# Pico_T61_Keyboard_R1.net
KiCad netlist of a schematic drawn in EAGLE
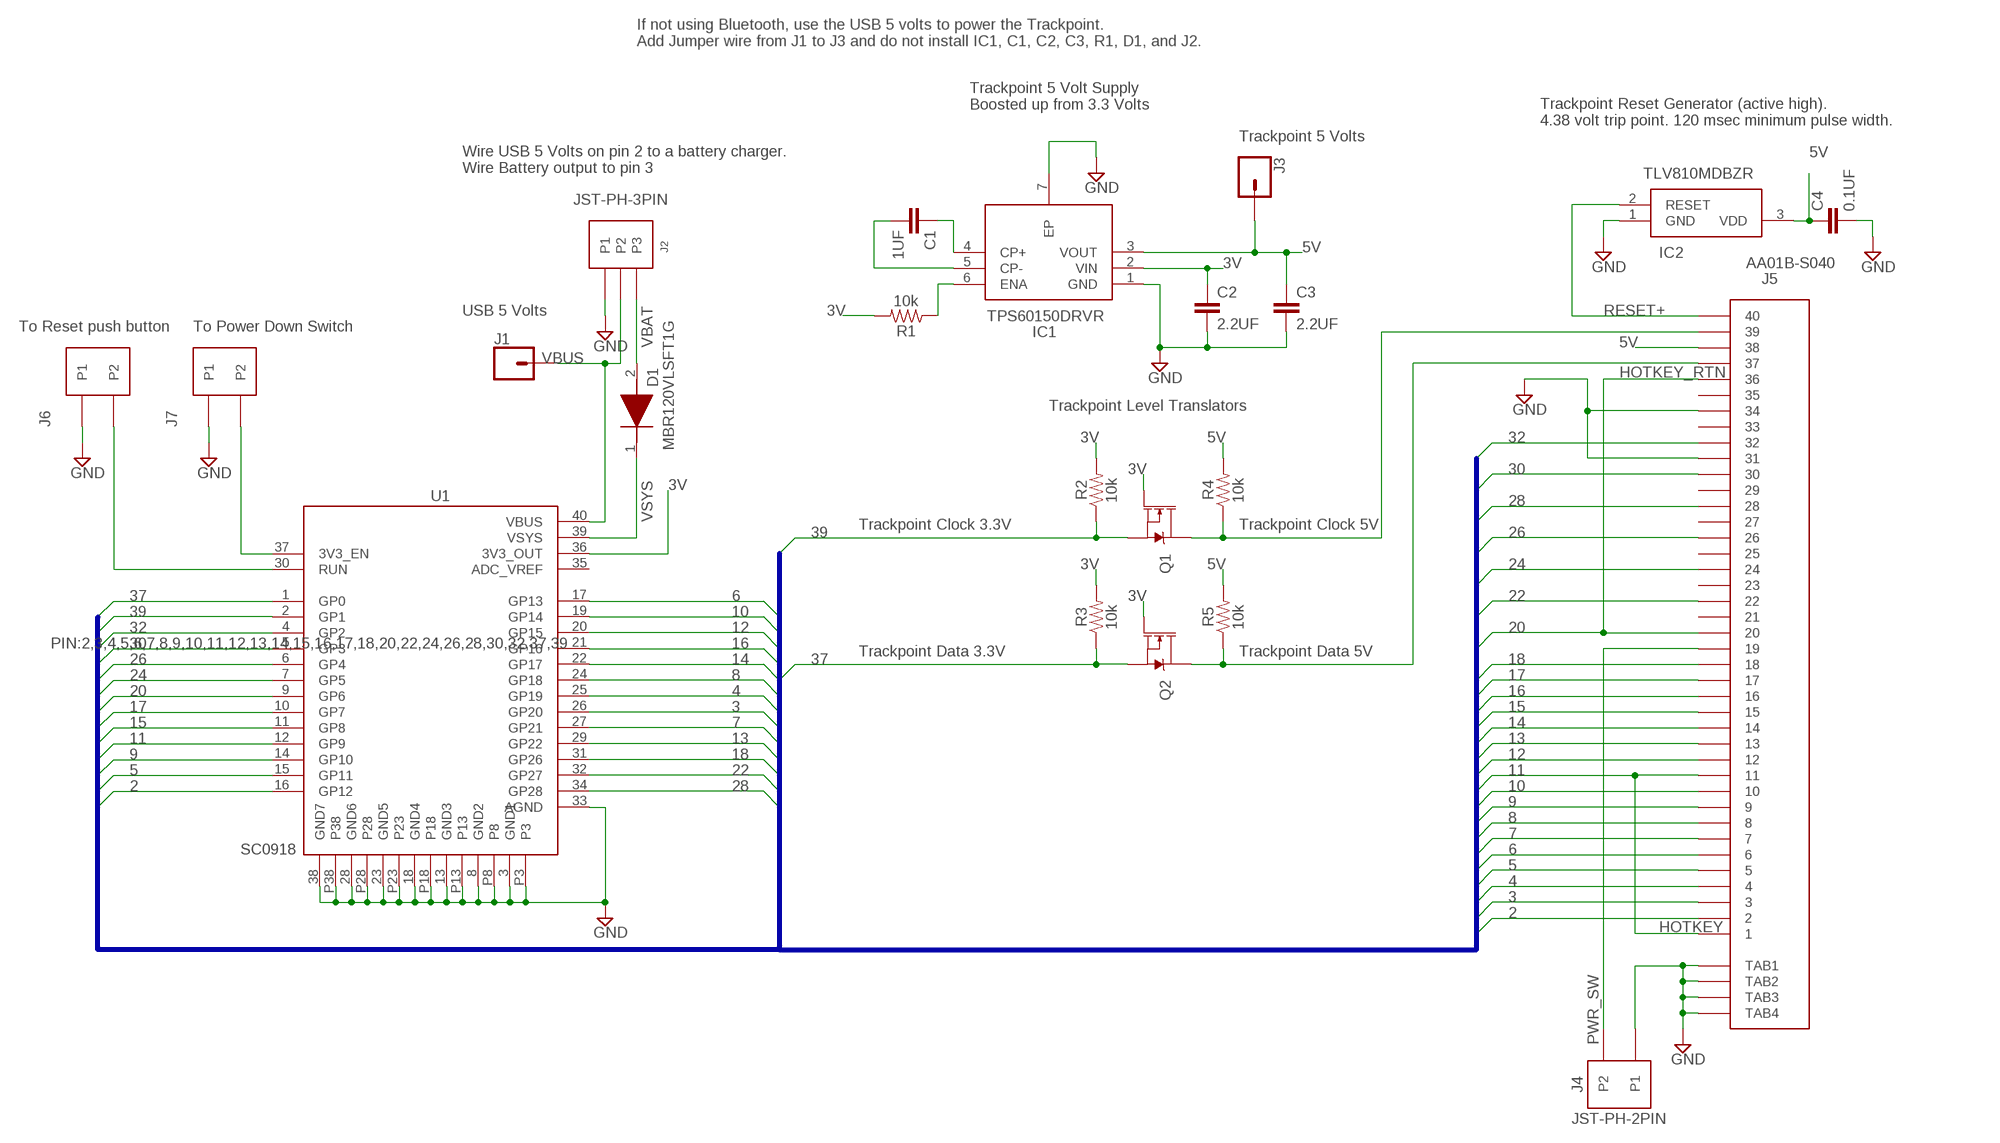
[diagram p0: schematic, sheet 1]

(export (version "E")
  (design (tool "Eeschema 10.0.6"))
  (components
    (comp (ref "C1")
      (value "1UF")
      (footprint "eagle-import:0603_CAP")
      (libsource (lib "eagle-import") (part "0603_CAP"))
    )
    (comp (ref "C2")
      (value "2.2UF")
      (footprint "eagle-import:0603_CAP")
      (libsource (lib "eagle-import") (part "0603_CAP"))
    )
    (comp (ref "C3")
      (value "2.2UF")
      (footprint "eagle-import:0603_CAP")
      (libsource (lib "eagle-import") (part "0603_CAP"))
    )
    (comp (ref "C4")
      (value "0.1UF")
      (footprint "eagle-import:0603_CAP")
      (libsource (lib "eagle-import") (part "0603_CAP"))
    )
    (comp (ref "D1")
      (value "MBR120VLSFT1G")
      (footprint "eagle-import:SODFL3616X98N")
      (fields (field (name "MOUSER_PART_NUMBER") "863-MBR120VLSFT1G"))
      (libsource (lib "eagle-import") (part "MBR120VLSFT1G"))
    )
    (comp (ref "IC1")
      (value "TPS60150DRVR")
      (footprint "eagle-import:SON65P200X200X80-7N")
      (fields (field (name "MOUSER_PART_NUMBER") "595-TPS60150DRVR"))
      (libsource (lib "eagle-import") (part "TPS60150DRVR"))
    )
    (comp (ref "IC2")
      (value "TLV810MDBZR")
      (footprint "eagle-import:SOT95P237X112-3N")
      (fields (field (name "MOUSER_PART_NUMBER") "595-TLV810MDBZR"))
      (libsource (lib "eagle-import") (part "TLV810MDBZR"))
    )
    (comp (ref "J1")
      (value "CONN_01")
      (footprint "eagle-import:1X01")
      (libsource (lib "eagle-import") (part "CONN_01"))
    )
    (comp (ref "J2")
      (value "JST-PH-3PIN")
      (footprint "eagle-import:JST-PH-3PIN")
      (libsource (lib "eagle-import") (part "JST-PH-3PIN"))
    )
    (comp (ref "J3")
      (value "CONN_01")
      (footprint "eagle-import:1X01")
      (libsource (lib "eagle-import") (part "CONN_01"))
    )
    (comp (ref "J4")
      (value "JST-PH-2PIN")
      (footprint "eagle-import:JST-PH-2PIN")
      (libsource (lib "eagle-import") (part "JST-PH-2PIN"))
    )
    (comp (ref "J5")
      (value "AA01B-S040")
      (footprint "eagle-import:WM6787_AA01B")
      (libsource (lib "eagle-import") (part "WM6787_A01B"))
    )
    (comp (ref "J6")
      (value "JST-PH-2PIN")
      (footprint "eagle-import:JST-PH-2PIN")
      (libsource (lib "eagle-import") (part "JST-PH-2PIN"))
    )
    (comp (ref "J7")
      (value "JST-PH-2PIN")
      (footprint "eagle-import:JST-PH-2PIN")
      (libsource (lib "eagle-import") (part "JST-PH-2PIN"))
    )
    (comp (ref "Q1")
      (value "220mA/50V/3.5Ω")
      (footprint "eagle-import:SOT23-3")
      (libsource (lib "eagle-import") (part "MOSFET-NCH-BSS138"))
    )
    (comp (ref "Q2")
      (value "220mA/50V/3.5Ω")
      (footprint "eagle-import:SOT23-3")
      (libsource (lib "eagle-import") (part "MOSFET-NCH-BSS138"))
    )
    (comp (ref "R1")
      (value "10k")
      (footprint "eagle-import:0603")
      (libsource (lib "eagle-import") (part "10KOHM-0603-1/10W-1%"))
    )
    (comp (ref "R2")
      (value "10k")
      (footprint "eagle-import:0603")
      (libsource (lib "eagle-import") (part "10KOHM-0603-1/10W-1%"))
    )
    (comp (ref "R3")
      (value "10k")
      (footprint "eagle-import:0603")
      (libsource (lib "eagle-import") (part "10KOHM-0603-1/10W-1%"))
    )
    (comp (ref "R4")
      (value "10k")
      (footprint "eagle-import:0603")
      (libsource (lib "eagle-import") (part "10KOHM-0603-1/10W-1%"))
    )
    (comp (ref "R5")
      (value "10k")
      (footprint "eagle-import:0603")
      (libsource (lib "eagle-import") (part "10KOHM-0603-1/10W-1%"))
    )
    (comp (ref "U1")
      (value "SC0918")
      (footprint "eagle-import:MODULE_SC0918")
      (fields (field (name "MF") "Raspberry Pi"))
      (libsource (lib "eagle-import") (part "SC0918"))
    )
  )
  (nets
    (net (code "2") (name "/2") (class "Default")
      (node (ref "J5") (pin "P$2") (pinfunction "2_P$2") (pintype "bidirectional"))
      (node (ref "U1") (pin "16") (pinfunction "GP12_16") (pintype "bidirectional"))
    )
    (net (code "3") (name "/3") (class "Default")
      (node (ref "J5") (pin "P$3") (pinfunction "3_P$3") (pintype "bidirectional"))
      (node (ref "U1") (pin "26") (pinfunction "GP20_26") (pintype "bidirectional"))
    )
    (net (code "4") (name "/3V") (class "Default")
      (node (ref "C2") (pin "1") (pinfunction "1_1") (pintype "passive"))
      (node (ref "IC1") (pin "2") (pinfunction "VIN_2") (pintype "bidirectional"))
      (node (ref "Q1") (pin "1") (pinfunction "G_1") (pintype "bidirectional"))
      (node (ref "Q2") (pin "1") (pinfunction "G_1") (pintype "bidirectional"))
      (node (ref "R1") (pin "2") (pinfunction "2_2") (pintype "passive"))
      (node (ref "R2") (pin "2") (pinfunction "2_2") (pintype "passive"))
      (node (ref "R3") (pin "2") (pinfunction "2_2") (pintype "passive"))
      (node (ref "U1") (pin "36") (pinfunction "3V3_OUT_36") (pintype "power_in"))
    )
    (net (code "5") (name "/4") (class "Default")
      (node (ref "J5") (pin "P$4") (pinfunction "4_P$4") (pintype "bidirectional"))
      (node (ref "U1") (pin "25") (pinfunction "GP19_25") (pintype "bidirectional"))
    )
    (net (code "6") (name "/5") (class "Default")
      (node (ref "J5") (pin "P$5") (pinfunction "5_P$5") (pintype "bidirectional"))
      (node (ref "U1") (pin "15") (pinfunction "GP11_15") (pintype "bidirectional"))
    )
    (net (code "7") (name "/5V") (class "Default")
      (node (ref "C3") (pin "1") (pinfunction "1_1") (pintype "passive"))
      (node (ref "C4") (pin "1") (pinfunction "1_1") (pintype "passive"))
      (node (ref "IC1") (pin "3") (pinfunction "VOUT_3") (pintype "bidirectional"))
      (node (ref "IC2") (pin "3") (pinfunction "VDD_3") (pintype "bidirectional"))
      (node (ref "J3") (pin "1") (pinfunction "1_1") (pintype "passive"))
      (node (ref "J5") (pin "P$38") (pinfunction "38_P$38") (pintype "bidirectional"))
      (node (ref "R4") (pin "2") (pinfunction "2_2") (pintype "passive"))
      (node (ref "R5") (pin "2") (pinfunction "2_2") (pintype "passive"))
    )
    (net (code "8") (name "/6") (class "Default")
      (node (ref "J5") (pin "P$6") (pinfunction "6_P$6") (pintype "bidirectional"))
      (node (ref "U1") (pin "17") (pinfunction "GP13_17") (pintype "bidirectional"))
    )
    (net (code "9") (name "/7") (class "Default")
      (node (ref "J5") (pin "P$7") (pinfunction "7_P$7") (pintype "bidirectional"))
      (node (ref "U1") (pin "27") (pinfunction "GP21_27") (pintype "bidirectional"))
    )
    (net (code "10") (name "/8") (class "Default")
      (node (ref "J5") (pin "P$8") (pinfunction "8_P$8") (pintype "bidirectional"))
      (node (ref "U1") (pin "24") (pinfunction "GP18_24") (pintype "bidirectional"))
    )
    (net (code "11") (name "/9") (class "Default")
      (node (ref "J5") (pin "P$9") (pinfunction "9_P$9") (pintype "bidirectional"))
      (node (ref "U1") (pin "14") (pinfunction "GP10_14") (pintype "bidirectional"))
    )
    (net (code "12") (name "/10") (class "Default")
      (node (ref "J5") (pin "P$10") (pinfunction "10_P$10") (pintype "bidirectional"))
      (node (ref "U1") (pin "19") (pinfunction "GP14_19") (pintype "bidirectional"))
    )
    (net (code "13") (name "/11") (class "Default")
      (node (ref "J5") (pin "P$1") (pinfunction "1_P$1") (pintype "bidirectional"))
      (node (ref "J5") (pin "P$11") (pinfunction "11_P$11") (pintype "bidirectional"))
      (node (ref "U1") (pin "12") (pinfunction "GP9_12") (pintype "bidirectional"))
    )
    (net (code "14") (name "/12") (class "Default")
      (node (ref "J5") (pin "P$12") (pinfunction "12_P$12") (pintype "bidirectional"))
      (node (ref "U1") (pin "20") (pinfunction "GP15_20") (pintype "bidirectional"))
    )
    (net (code "15") (name "/13") (class "Default")
      (node (ref "J5") (pin "P$13") (pinfunction "13_P$13") (pintype "bidirectional"))
      (node (ref "U1") (pin "29") (pinfunction "GP22_29") (pintype "bidirectional"))
    )
    (net (code "16") (name "/14") (class "Default")
      (node (ref "J5") (pin "P$14") (pinfunction "14_P$14") (pintype "bidirectional"))
      (node (ref "U1") (pin "22") (pinfunction "GP17_22") (pintype "bidirectional"))
    )
    (net (code "17") (name "/15") (class "Default")
      (node (ref "J5") (pin "P$15") (pinfunction "15_P$15") (pintype "bidirectional"))
      (node (ref "U1") (pin "11") (pinfunction "GP8_11") (pintype "bidirectional"))
    )
    (net (code "18") (name "/16") (class "Default")
      (node (ref "J5") (pin "P$16") (pinfunction "16_P$16") (pintype "bidirectional"))
      (node (ref "U1") (pin "21") (pinfunction "GP16_21") (pintype "bidirectional"))
    )
    (net (code "19") (name "/17") (class "Default")
      (node (ref "J5") (pin "P$17") (pinfunction "17_P$17") (pintype "bidirectional"))
      (node (ref "U1") (pin "10") (pinfunction "GP7_10") (pintype "bidirectional"))
    )
    (net (code "20") (name "/18") (class "Default")
      (node (ref "J5") (pin "P$18") (pinfunction "18_P$18") (pintype "bidirectional"))
      (node (ref "U1") (pin "31") (pinfunction "GP26_31") (pintype "bidirectional"))
    )
    (net (code "21") (name "/20") (class "Default")
      (node (ref "J5") (pin "P$20") (pinfunction "20_P$20") (pintype "bidirectional"))
      (node (ref "J5") (pin "P$36") (pinfunction "36_P$36") (pintype "bidirectional"))
      (node (ref "U1") (pin "9") (pinfunction "GP6_9") (pintype "bidirectional"))
    )
    (net (code "22") (name "/22") (class "Default")
      (node (ref "J5") (pin "P$22") (pinfunction "22_P$22") (pintype "bidirectional"))
      (node (ref "U1") (pin "32") (pinfunction "GP27_32") (pintype "bidirectional"))
    )
    (net (code "23") (name "/24") (class "Default")
      (node (ref "J5") (pin "P$24") (pinfunction "24_P$24") (pintype "bidirectional"))
      (node (ref "U1") (pin "7") (pinfunction "GP5_7") (pintype "bidirectional"))
    )
    (net (code "24") (name "/26") (class "Default")
      (node (ref "J5") (pin "P$26") (pinfunction "26_P$26") (pintype "bidirectional"))
      (node (ref "U1") (pin "6") (pinfunction "GP4_6") (pintype "bidirectional"))
    )
    (net (code "25") (name "/28") (class "Default")
      (node (ref "J5") (pin "P$28") (pinfunction "28_P$28") (pintype "bidirectional"))
      (node (ref "U1") (pin "34") (pinfunction "GP28_34") (pintype "bidirectional"))
    )
    (net (code "26") (name "/30") (class "Default")
      (node (ref "J5") (pin "P$30") (pinfunction "30_P$30") (pintype "bidirectional"))
      (node (ref "U1") (pin "5") (pinfunction "GP3_5") (pintype "bidirectional"))
    )
    (net (code "27") (name "/32") (class "Default")
      (node (ref "J5") (pin "P$32") (pinfunction "32_P$32") (pintype "bidirectional"))
      (node (ref "U1") (pin "4") (pinfunction "GP2_4") (pintype "bidirectional"))
    )
    (net (code "28") (name "/37") (class "Default")
      (node (ref "Q2") (pin "2") (pinfunction "S_2") (pintype "bidirectional"))
      (node (ref "R3") (pin "1") (pinfunction "1_1") (pintype "passive"))
      (node (ref "U1") (pin "1") (pinfunction "GP0_1") (pintype "bidirectional"))
    )
    (net (code "29") (name "/39") (class "Default")
      (node (ref "Q1") (pin "2") (pinfunction "S_2") (pintype "bidirectional"))
      (node (ref "R2") (pin "1") (pinfunction "1_1") (pintype "passive"))
      (node (ref "U1") (pin "2") (pinfunction "GP1_2") (pintype "bidirectional"))
    )
    (net (code "30") (name "/ADC_VREF") (class "Default")
      (node (ref "U1") (pin "35") (pinfunction "ADC_VREF_35") (pintype "power_in"))
    )
    (net (code "31") (name "/PWR_SW") (class "Default")
      (node (ref "J4") (pin "P$2") (pinfunction "P2_P$2") (pintype "bidirectional"))
      (node (ref "J5") (pin "P$19") (pinfunction "19_P$19") (pintype "bidirectional"))
    )
    (net (code "32") (name "/RESET+") (class "Default")
      (node (ref "IC2") (pin "2") (pinfunction "RESET_2") (pintype "bidirectional"))
      (node (ref "J5") (pin "P$40") (pinfunction "40_P$40") (pintype "bidirectional"))
    )
    (net (code "33") (name "/VBAT") (class "Default")
      (node (ref "D1") (pin "2") (pinfunction "A_2") (pintype "bidirectional"))
      (node (ref "J2") (pin "P$3") (pinfunction "P3_P$3") (pintype "bidirectional"))
    )
    (net (code "34") (name "/VBUS") (class "Default")
      (node (ref "J1") (pin "1") (pinfunction "1_1") (pintype "passive"))
      (node (ref "J2") (pin "P$2") (pinfunction "P2_P$2") (pintype "bidirectional"))
      (node (ref "U1") (pin "40") (pinfunction "VBUS_40") (pintype "power_in"))
    )
    (net (code "35") (name "/VSYS") (class "Default")
      (node (ref "D1") (pin "1") (pinfunction "K_1") (pintype "bidirectional"))
      (node (ref "U1") (pin "39") (pinfunction "VSYS_39") (pintype "power_in"))
    )
    (net (code "37") (name "GND") (class "Default")
      (node (ref "C2") (pin "2") (pinfunction "2_2") (pintype "passive"))
      (node (ref "C3") (pin "2") (pinfunction "2_2") (pintype "passive"))
      (node (ref "C4") (pin "2") (pinfunction "2_2") (pintype "passive"))
      (node (ref "IC1") (pin "1") (pinfunction "GND_1") (pintype "bidirectional"))
      (node (ref "IC1") (pin "7") (pinfunction "EP_7") (pintype "bidirectional"))
      (node (ref "IC2") (pin "1") (pinfunction "GND_1") (pintype "bidirectional"))
      (node (ref "J2") (pin "P$1") (pinfunction "P1_P$1") (pintype "bidirectional"))
      (node (ref "J4") (pin "P$1") (pinfunction "P1_P$1") (pintype "bidirectional"))
      (node (ref "J5") (pin "P$31") (pinfunction "31_P$31") (pintype "bidirectional"))
      (node (ref "J5") (pin "P$34") (pinfunction "34_P$34") (pintype "bidirectional"))
      (node (ref "J5") (pin "TAB1") (pinfunction "TAB1_TAB1") (pintype "bidirectional"))
      (node (ref "J5") (pin "TAB2") (pinfunction "TAB2_TAB2") (pintype "bidirectional"))
      (node (ref "J5") (pin "TAB3") (pinfunction "TAB3_TAB3") (pintype "bidirectional"))
      (node (ref "J5") (pin "TAB4") (pinfunction "TAB4_TAB4") (pintype "bidirectional"))
      (node (ref "J6") (pin "P$1") (pinfunction "P1_P$1") (pintype "bidirectional"))
      (node (ref "J7") (pin "P$1") (pinfunction "P1_P$1") (pintype "bidirectional"))
      (node (ref "U1") (pin "13") (pinfunction "GND3_13") (pintype "power_in"))
      (node (ref "U1") (pin "18") (pinfunction "GND4_18") (pintype "power_in"))
      (node (ref "U1") (pin "23") (pinfunction "GND5_23") (pintype "power_in"))
      (node (ref "U1") (pin "28") (pinfunction "GND6_28") (pintype "power_in"))
      (node (ref "U1") (pin "3") (pinfunction "GND1_3") (pintype "power_in"))
      (node (ref "U1") (pin "33") (pinfunction "AGND_33") (pintype "power_in"))
      (node (ref "U1") (pin "38") (pinfunction "GND7_38") (pintype "power_in"))
      (node (ref "U1") (pin "8") (pinfunction "GND2_8") (pintype "power_in"))
      (node (ref "U1") (pin "P13") (pinfunction "P13_P13") (pintype "power_in"))
      (node (ref "U1") (pin "P18") (pinfunction "P18_P18") (pintype "power_in"))
      (node (ref "U1") (pin "P23") (pinfunction "P23_P23") (pintype "power_in"))
      (node (ref "U1") (pin "P28") (pinfunction "P28_P28") (pintype "power_in"))
      (node (ref "U1") (pin "P3") (pinfunction "P3_P3") (pintype "power_in"))
      (node (ref "U1") (pin "P38") (pinfunction "P38_P38") (pintype "power_in"))
      (node (ref "U1") (pin "P8") (pinfunction "P8_P8") (pintype "power_in"))
    )
    (net (code "38") (name "Net-(IC1-CP+)") (class "Default")
      (node (ref "C1") (pin "1") (pinfunction "1_1") (pintype "passive"))
      (node (ref "IC1") (pin "4") (pinfunction "CP+_4") (pintype "bidirectional"))
    )
    (net (code "39") (name "Net-(IC1-CP-)") (class "Default")
      (node (ref "C1") (pin "2") (pinfunction "2_2") (pintype "passive"))
      (node (ref "IC1") (pin "5") (pinfunction "CP-_5") (pintype "bidirectional"))
    )
    (net (code "40") (name "Net-(IC1-ENA)") (class "Default")
      (node (ref "IC1") (pin "6") (pinfunction "ENA_6") (pintype "bidirectional"))
      (node (ref "R1") (pin "1") (pinfunction "1_1") (pintype "passive"))
    )
    (net (code "41") (name "Net-(J5-37)") (class "Default")
      (node (ref "J5") (pin "P$37") (pinfunction "37_P$37") (pintype "bidirectional"))
      (node (ref "Q2") (pin "3") (pinfunction "D_3") (pintype "bidirectional"))
      (node (ref "R5") (pin "1") (pinfunction "1_1") (pintype "passive"))
    )
    (net (code "42") (name "Net-(J5-39)") (class "Default")
      (node (ref "J5") (pin "P$39") (pinfunction "39_P$39") (pintype "bidirectional"))
      (node (ref "Q1") (pin "3") (pinfunction "D_3") (pintype "bidirectional"))
      (node (ref "R4") (pin "1") (pinfunction "1_1") (pintype "passive"))
    )
    (net (code "43") (name "Net-(J6-P2)") (class "Default")
      (node (ref "J6") (pin "P$2") (pinfunction "P2_P$2") (pintype "bidirectional"))
      (node (ref "U1") (pin "30") (pinfunction "RUN_30") (pintype "input"))
    )
    (net (code "44") (name "Net-(J7-P2)") (class "Default")
      (node (ref "J7") (pin "P$2") (pinfunction "P2_P$2") (pintype "bidirectional"))
      (node (ref "U1") (pin "37") (pinfunction "3V3_EN_37") (pintype "input"))
    )
    (net (code "45") (name "unconnected-(J5-21-PadP$21)") (class "Default")
      (node (ref "J5") (pin "P$21") (pinfunction "21_P$21") (pintype "bidirectional"))
    )
    (net (code "46") (name "unconnected-(J5-23-PadP$23)") (class "Default")
      (node (ref "J5") (pin "P$23") (pinfunction "23_P$23") (pintype "bidirectional"))
    )
    (net (code "47") (name "unconnected-(J5-25-PadP$25)") (class "Default")
      (node (ref "J5") (pin "P$25") (pinfunction "25_P$25") (pintype "bidirectional"))
    )
    (net (code "48") (name "unconnected-(J5-27-PadP$27)") (class "Default")
      (node (ref "J5") (pin "P$27") (pinfunction "27_P$27") (pintype "bidirectional"))
    )
    (net (code "49") (name "unconnected-(J5-29-PadP$29)") (class "Default")
      (node (ref "J5") (pin "P$29") (pinfunction "29_P$29") (pintype "bidirectional"))
    )
    (net (code "50") (name "unconnected-(J5-33-PadP$33)") (class "Default")
      (node (ref "J5") (pin "P$33") (pinfunction "33_P$33") (pintype "bidirectional"))
    )
    (net (code "51") (name "unconnected-(J5-35-PadP$35)") (class "Default")
      (node (ref "J5") (pin "P$35") (pinfunction "35_P$35") (pintype "bidirectional"))
    )
  )
)
